# WIFI-Switch.net
KiCad netlist of a schematic drawn in EAGLE
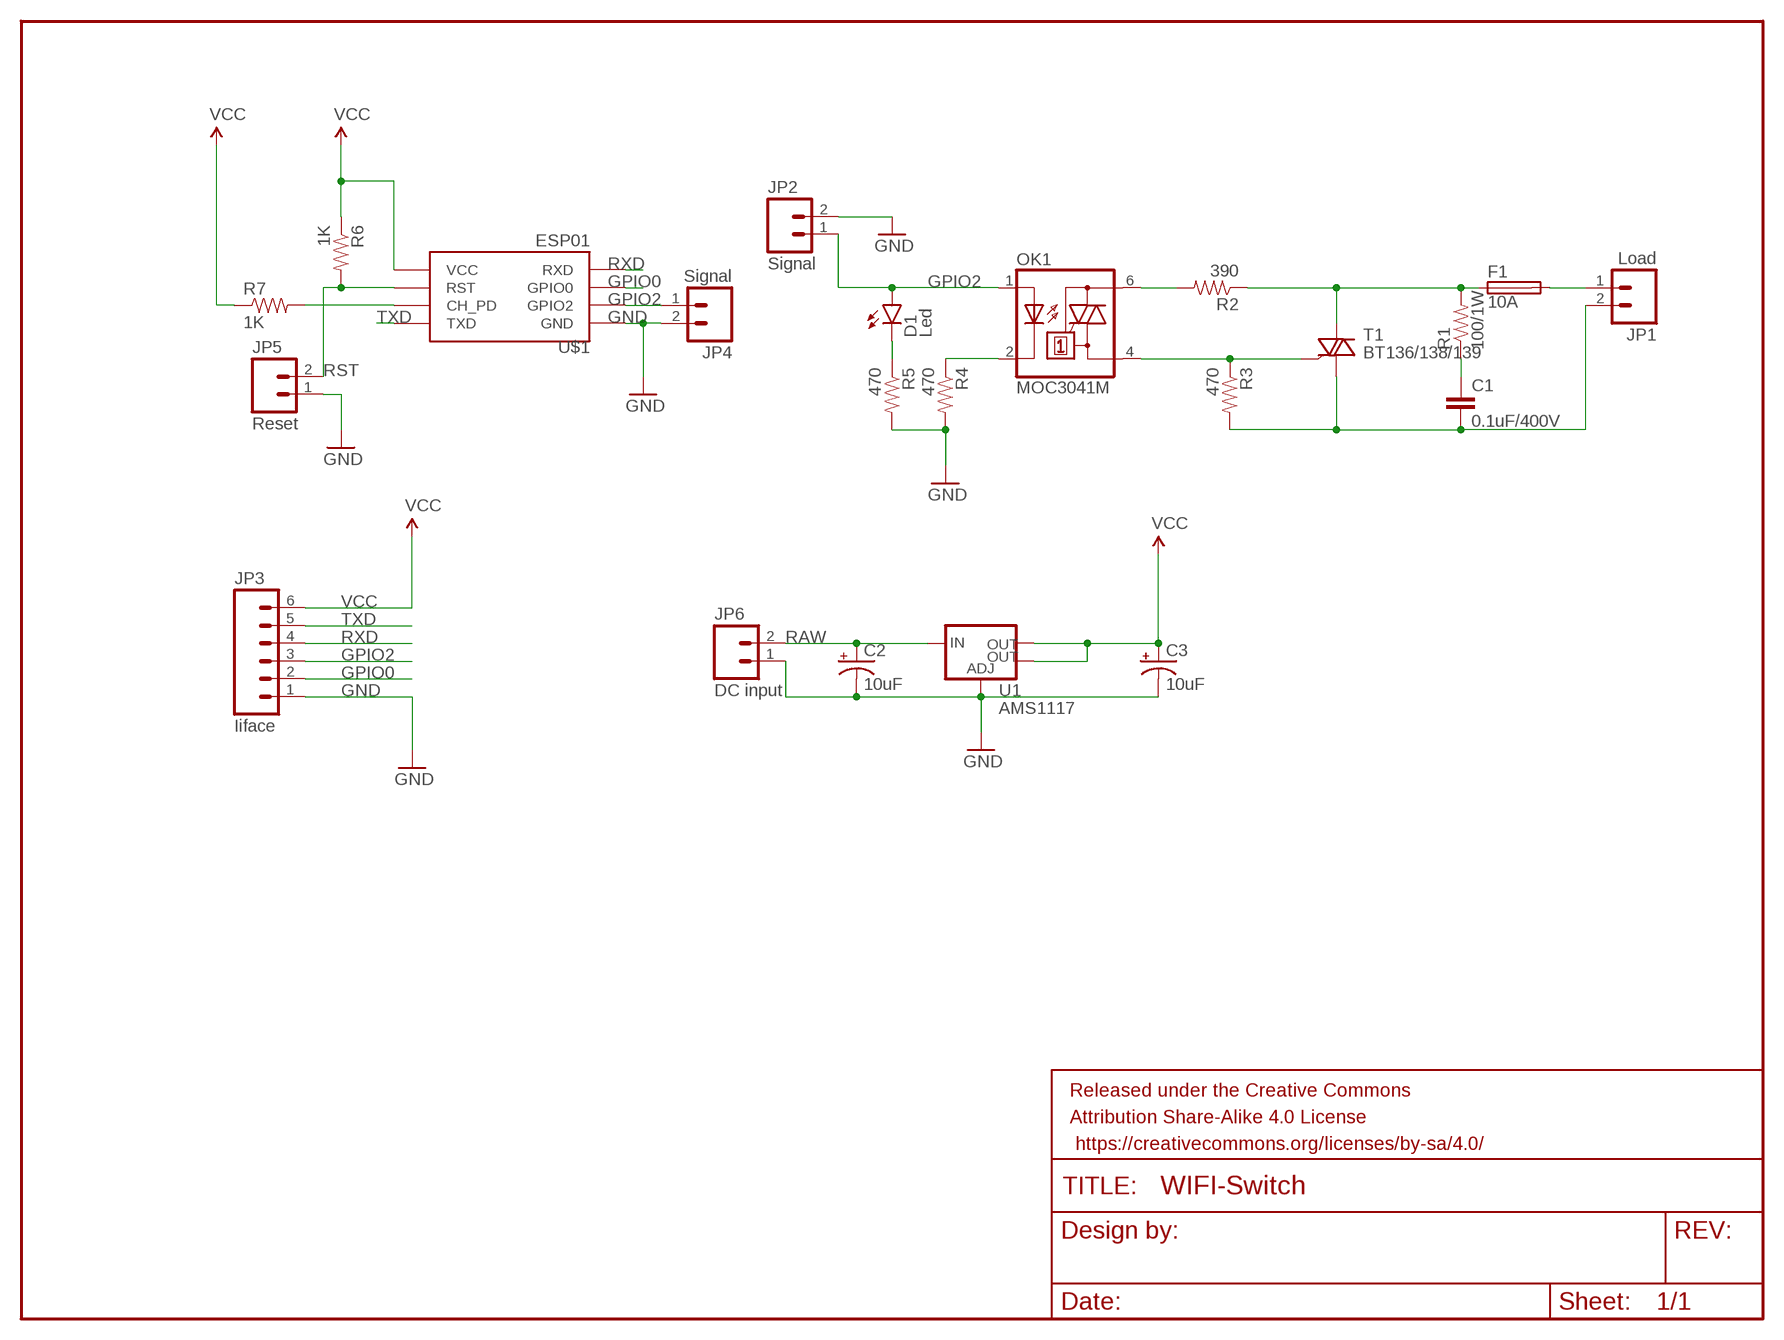
[diagram p0: schematic, sheet 1]

(export (version "E")
  (design (tool "Eeschema 10.0.6"))
  (components
    (comp (ref "C1")
      (value "0.1uF/400V")
      (footprint "eagle-import:C10B4")
      (libsource (lib "eagle-import") (part "C10/4"))
    )
    (comp (ref "C2")
      (value "10uF")
      (footprint "eagle-import:EIA3216")
      (libsource (lib "eagle-import") (part "CAP_POL1206"))
    )
    (comp (ref "C3")
      (value "10uF")
      (footprint "eagle-import:EIA3216")
      (libsource (lib "eagle-import") (part "CAP_POL1206"))
    )
    (comp (ref "D1")
      (value "Led")
      (footprint "eagle-import:LED3MM")
      (libsource (lib "eagle-import") (part "LED3MM"))
    )
    (comp (ref "F1")
      (value "10A")
      (footprint "eagle-import:SH22,5A")
      (libsource (lib "eagle-import") (part "SH22,5A"))
    )
    (comp (ref "FRAME1")
      (value "FRAME-LETTER")
      (footprint "eagle-import:CREATIVE_COMMONS")
      (libsource (lib "eagle-import") (part "FRAME-LETTER"))
    )
    (comp (ref "JP1")
      (value "Load")
      (footprint "eagle-import:SCREWTERMINAL-5MM-2")
      (libsource (lib "eagle-import") (part "M025MM"))
    )
    (comp (ref "JP2")
      (value "Signal")
      (footprint "eagle-import:1X02_LOCK")
      (libsource (lib "eagle-import") (part "M02LOCK"))
    )
    (comp (ref "JP3")
      (value "Iiface")
      (footprint "eagle-import:1X06_FEMALE_LOCK.010")
      (libsource (lib "eagle-import") (part "M06FEMALE_LOCK"))
    )
    (comp (ref "JP4")
      (value "Signal")
      (footprint "eagle-import:1X02_LOCK")
      (libsource (lib "eagle-import") (part "M02LOCK"))
    )
    (comp (ref "JP5")
      (value "Reset")
      (footprint "eagle-import:1X02_LOCK")
      (libsource (lib "eagle-import") (part "M02LOCK"))
    )
    (comp (ref "JP6")
      (value "DC input")
      (footprint "eagle-import:1X02_LOCK")
      (libsource (lib "eagle-import") (part "M02LOCK"))
    )
    (comp (ref "OK1")
      (value "MOC3041M")
      (footprint "eagle-import:DIL06")
      (libsource (lib "eagle-import") (part "MOC3041M"))
    )
    (comp (ref "R1")
      (value "100/1W")
      (footprint "eagle-import:AXIAL-0.8")
      (libsource (lib "eagle-import") (part "RESISTORPTH-2W"))
    )
    (comp (ref "R2")
      (value "390")
      (footprint "eagle-import:AXIAL-0.1")
      (libsource (lib "eagle-import") (part "RESISTORPTH-1/4W-VERT"))
    )
    (comp (ref "R3")
      (value "470")
      (footprint "eagle-import:AXIAL-0.4")
      (libsource (lib "eagle-import") (part "RESISTORPTH-1/4W"))
    )
    (comp (ref "R4")
      (value "470")
      (footprint "eagle-import:AXIAL-0.1")
      (libsource (lib "eagle-import") (part "RESISTORPTH-1/4W-VERT"))
    )
    (comp (ref "R5")
      (value "470")
      (footprint "eagle-import:AXIAL-0.1")
      (libsource (lib "eagle-import") (part "RESISTORPTH-1/4W-VERT"))
    )
    (comp (ref "R6")
      (value "1K")
      (footprint "eagle-import:AXIAL-0.1")
      (libsource (lib "eagle-import") (part "RESISTORPTH-1/4W-VERT"))
    )
    (comp (ref "R7")
      (value "1K")
      (footprint "eagle-import:AXIAL-0.1")
      (libsource (lib "eagle-import") (part "RESISTORPTH-1/4W-VERT"))
    )
    (comp (ref "T1")
      (value "BT136/138/139")
      (footprint "eagle-import:TO220BV")
      (libsource (lib "eagle-import") (part "BT138-V"))
    )
    (comp (ref "U$1")
      (value "ESP01")
      (footprint "eagle-import:ESP01")
      (libsource (lib "eagle-import") (part "ESP01"))
    )
    (comp (ref "U1")
      (value "AMS1117")
      (footprint "eagle-import:SOT223")
      (libsource (lib "eagle-import") (part "V_REG_LM1117SOT223"))
    )
  )
  (nets
    (net (code "1") (name "/GPIO0") (class "Default")
      (node (ref "JP3") (pin "2") (pinfunction "2_2") (pintype "passive"))
      (node (ref "U$1") (pin "GPIO0") (pinfunction "GPIO0_GPIO0") (pintype "bidirectional"))
    )
    (net (code "2") (name "/GPIO2") (class "Default")
      (node (ref "D1") (pin "A") (pinfunction "A_A") (pintype "passive"))
      (node (ref "JP2") (pin "1") (pinfunction "1_1") (pintype "passive"))
      (node (ref "JP3") (pin "3") (pinfunction "3_3") (pintype "passive"))
      (node (ref "JP4") (pin "1") (pinfunction "1_1") (pintype "passive"))
      (node (ref "OK1") (pin "1") (pinfunction "A_1") (pintype "passive"))
      (node (ref "U$1") (pin "GPIO2") (pinfunction "GPIO2_GPIO2") (pintype "bidirectional"))
    )
    (net (code "3") (name "/RAW") (class "Default")
      (node (ref "C2") (pin "A") (pinfunction "+_A") (pintype "passive"))
      (node (ref "JP6") (pin "2") (pinfunction "2_2") (pintype "passive"))
      (node (ref "U1") (pin "3") (pinfunction "IN_3") (pintype "input"))
    )
    (net (code "4") (name "/RST") (class "Default")
      (node (ref "JP5") (pin "2") (pinfunction "2_2") (pintype "passive"))
      (node (ref "R6") (pin "P$2") (pinfunction "2_P$2") (pintype "passive"))
      (node (ref "U$1") (pin "RST") (pinfunction "RST_RST") (pintype "bidirectional"))
    )
    (net (code "5") (name "/RXD") (class "Default")
      (node (ref "JP3") (pin "4") (pinfunction "4_4") (pintype "passive"))
      (node (ref "U$1") (pin "RX") (pinfunction "RXD_RX") (pintype "bidirectional"))
    )
    (net (code "6") (name "/TXD") (class "Default")
      (node (ref "JP3") (pin "5") (pinfunction "5_5") (pintype "passive"))
      (node (ref "U$1") (pin "TX") (pinfunction "TXD_TX") (pintype "bidirectional"))
    )
    (net (code "7") (name "GND") (class "Default")
      (node (ref "C2") (pin "C") (pinfunction "-_C") (pintype "passive"))
      (node (ref "C3") (pin "C") (pinfunction "-_C") (pintype "passive"))
      (node (ref "JP2") (pin "2") (pinfunction "2_2") (pintype "passive"))
      (node (ref "JP3") (pin "1") (pinfunction "1_1") (pintype "passive"))
      (node (ref "JP4") (pin "2") (pinfunction "2_2") (pintype "passive"))
      (node (ref "JP5") (pin "1") (pinfunction "1_1") (pintype "passive"))
      (node (ref "JP6") (pin "1") (pinfunction "1_1") (pintype "passive"))
      (node (ref "R4") (pin "P$2") (pinfunction "2_P$2") (pintype "passive"))
      (node (ref "R5") (pin "P$2") (pinfunction "2_P$2") (pintype "passive"))
      (node (ref "U$1") (pin "GND") (pinfunction "GND_GND") (pintype "bidirectional"))
      (node (ref "U1") (pin "1") (pinfunction "ADJ_1") (pintype "input"))
    )
    (net (code "8") (name "Net-(D1-C)") (class "Default")
      (node (ref "D1") (pin "K") (pinfunction "C_K") (pintype "passive"))
      (node (ref "R5") (pin "P$1") (pinfunction "1_P$1") (pintype "passive"))
    )
    (net (code "9") (name "Net-(F1-Pad2)") (class "Default")
      (node (ref "F1") (pin "2") (pinfunction "2_2") (pintype "passive"))
      (node (ref "JP1") (pin "1") (pinfunction "1_1") (pintype "passive"))
    )
    (net (code "10") (name "Net-(OK1-A1)") (class "Default")
      (node (ref "OK1") (pin "4") (pinfunction "A1_4") (pintype "passive"))
      (node (ref "R3") (pin "P$1") (pinfunction "1_P$1") (pintype "passive"))
      (node (ref "T1") (pin "G") (pinfunction "G_G") (pintype "passive"))
    )
    (net (code "11") (name "Net-(OK1-A2)") (class "Default")
      (node (ref "OK1") (pin "6") (pinfunction "A2_6") (pintype "passive"))
      (node (ref "R2") (pin "P$2") (pinfunction "2_P$2") (pintype "passive"))
    )
    (net (code "12") (name "Net-(OK1-C)") (class "Default")
      (node (ref "OK1") (pin "2") (pinfunction "C_2") (pintype "passive"))
      (node (ref "R4") (pin "P$1") (pinfunction "1_P$1") (pintype "passive"))
    )
    (net (code "13") (name "Net-(R1-1)") (class "Default")
      (node (ref "C1") (pin "1") (pinfunction "1_1") (pintype "passive"))
      (node (ref "R1") (pin "P$1") (pinfunction "1_P$1") (pintype "passive"))
    )
    (net (code "14") (name "Net-(R1-2)") (class "Default")
      (node (ref "F1") (pin "1") (pinfunction "1_1") (pintype "passive"))
      (node (ref "R1") (pin "P$2") (pinfunction "2_P$2") (pintype "passive"))
      (node (ref "R2") (pin "P$1") (pinfunction "1_P$1") (pintype "passive"))
      (node (ref "T1") (pin "T2") (pinfunction "A2_T2") (pintype "passive"))
    )
    (net (code "15") (name "Net-(R3-2)") (class "Default")
      (node (ref "C1") (pin "2") (pinfunction "2_2") (pintype "passive"))
      (node (ref "JP1") (pin "2") (pinfunction "2_2") (pintype "passive"))
      (node (ref "R3") (pin "P$2") (pinfunction "2_P$2") (pintype "passive"))
      (node (ref "T1") (pin "T1") (pinfunction "A1_T1") (pintype "passive"))
    )
    (net (code "16") (name "Net-(R7-2)") (class "Default")
      (node (ref "R7") (pin "P$2") (pinfunction "2_P$2") (pintype "passive"))
      (node (ref "U$1") (pin "CH_PD") (pinfunction "CH_PD_CH_PD") (pintype "bidirectional"))
    )
    (net (code "17") (name "VCC") (class "Default")
      (node (ref "C3") (pin "A") (pinfunction "+_A") (pintype "passive"))
      (node (ref "JP3") (pin "6") (pinfunction "6_6") (pintype "passive"))
      (node (ref "R6") (pin "P$1") (pinfunction "1_P$1") (pintype "passive"))
      (node (ref "R7") (pin "P$1") (pinfunction "1_P$1") (pintype "passive"))
      (node (ref "U$1") (pin "VCC") (pinfunction "VCC_VCC") (pintype "bidirectional"))
      (node (ref "U1") (pin "2") (pinfunction "OUT_2") (pintype "output"))
      (node (ref "U1") (pin "4") (pinfunction "OUT_4") (pintype "output"))
    )
  )
)
